# TheRightHandPath.net
KiCad netlist of a schematic drawn in EAGLE
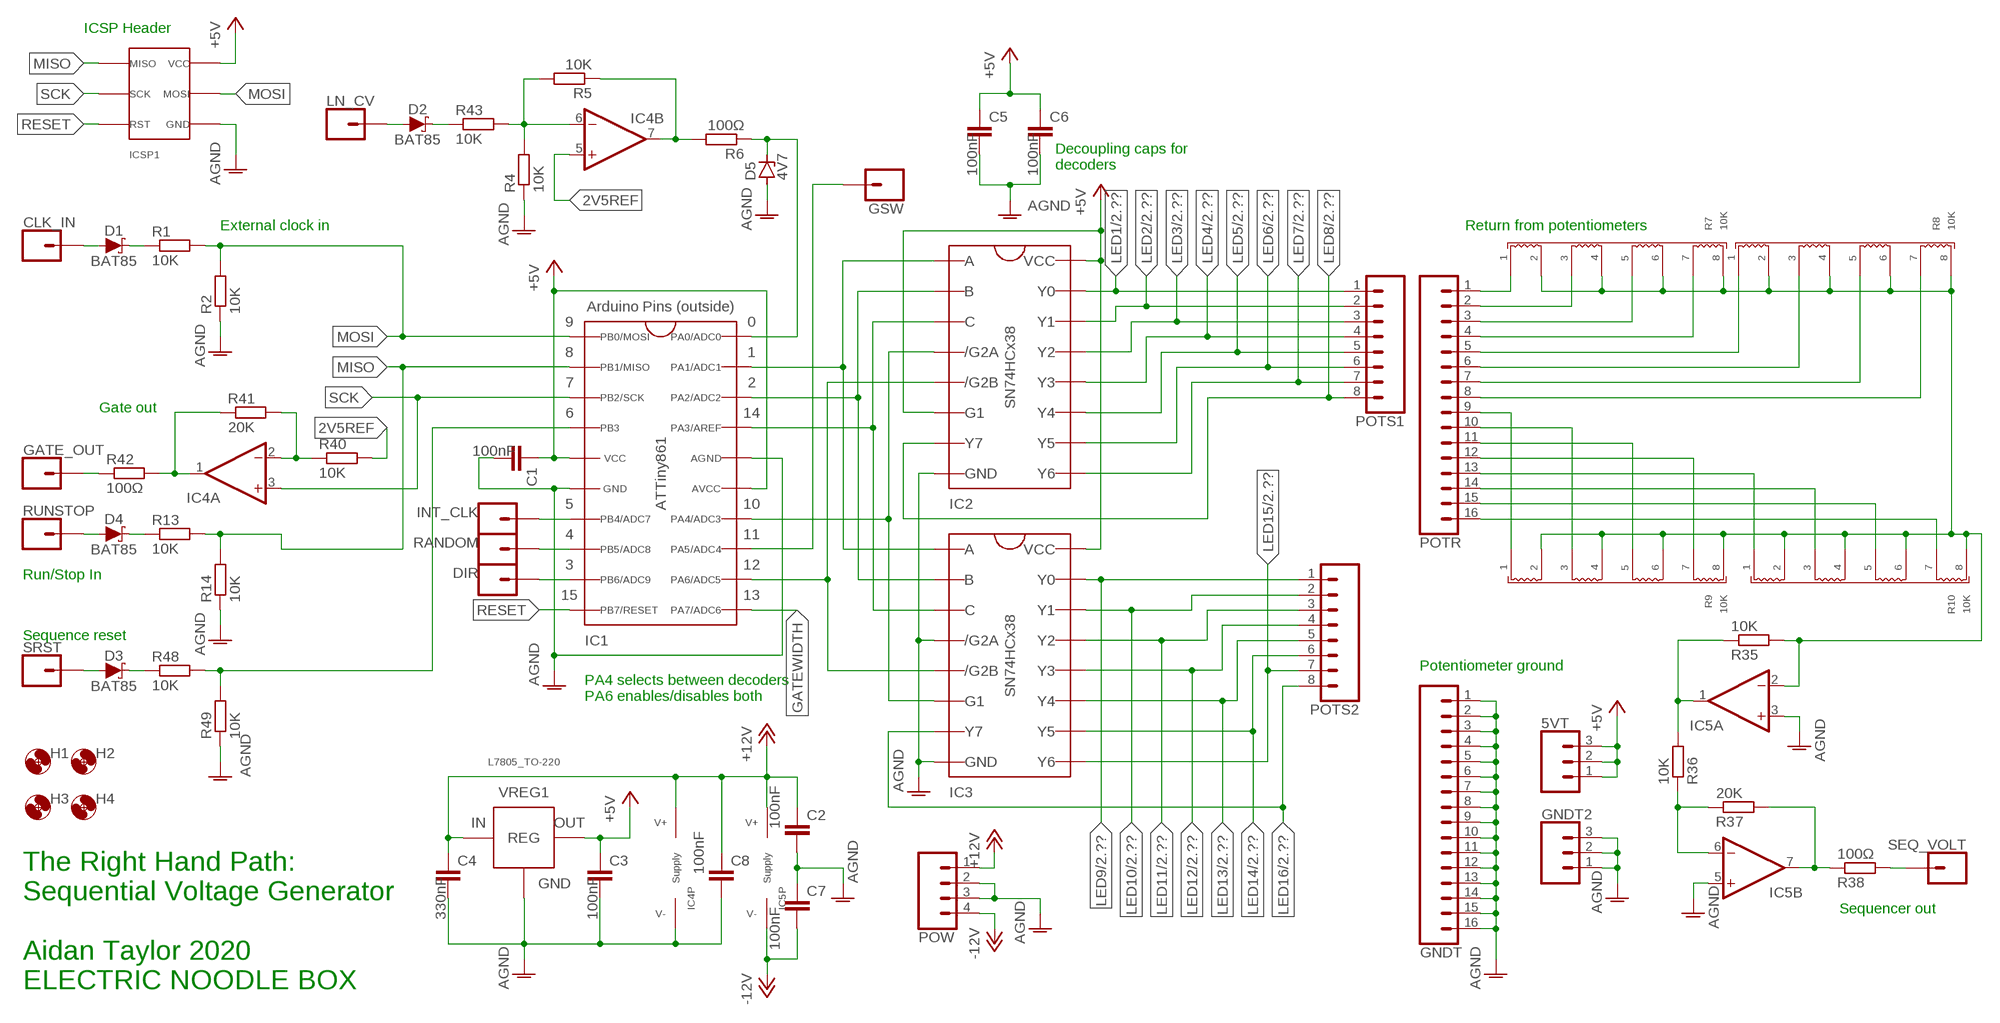
[diagram p0: schematic, sheet 1]
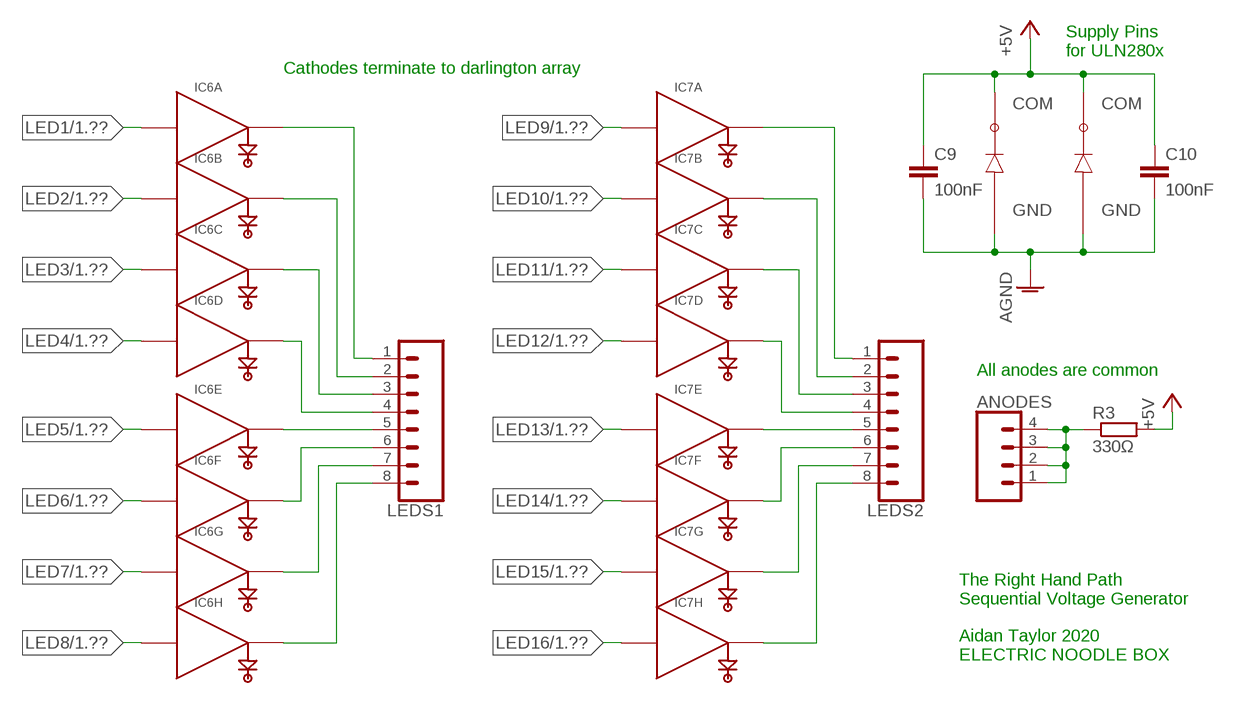
[diagram p1: schematic, sheet 2]

(export (version "E")
  (design (tool "Eeschema 10.0.6"))
  (components
    (comp (ref "ANODES")
      (value "4XWIREPAD")
      (footprint "eagle-import:1X04")
      (libsource (lib "eagle-import") (part "4XWIREPAD"))
    )
    (comp (ref "C9")
      (value "100nF")
      (footprint "eagle-import:C050-025X075")
      (libsource (lib "eagle-import") (part "C-EU050-025X075"))
    )
    (comp (ref "C10")
      (value "100nF")
      (footprint "eagle-import:C050-025X075")
      (libsource (lib "eagle-import") (part "C-EU050-025X075"))
    )
    (comp (ref "IC6")
      (value "ULN2801_DIP")
      (footprint "eagle-import:DIL18")
      (libsource (lib "eagle-import") (part "ULN2801_DIP"))
    )
    (comp (ref "IC7")
      (value "ULN2801_DIP")
      (footprint "eagle-import:DIL18")
      (libsource (lib "eagle-import") (part "ULN2801_DIP"))
    )
    (comp (ref "LEDS1")
      (value "8XWIREPAD")
      (footprint "eagle-import:1X08")
      (libsource (lib "eagle-import") (part "8XWIREPAD"))
    )
    (comp (ref "LEDS2")
      (value "8XWIREPAD")
      (footprint "eagle-import:1X08")
      (libsource (lib "eagle-import") (part "8XWIREPAD"))
    )
    (comp (ref "R3")
      (value "330Ω")
      (footprint "eagle-import:0207_10")
      (libsource (lib "eagle-import") (part "R-EU_0207/10"))
    )
    (comp (ref "5VT")
      (value "3XWIREPAD")
      (footprint "eagle-import:1X03")
      (libsource (lib "eagle-import") (part "3XWIREPAD"))
    )
    (comp (ref "C1")
      (value "100nF")
      (footprint "eagle-import:C050-025X075")
      (libsource (lib "eagle-import") (part "C-EU050-025X075"))
    )
    (comp (ref "C2")
      (value "100nF")
      (footprint "eagle-import:C050-025X075")
      (libsource (lib "eagle-import") (part "C-EU050-025X075"))
    )
    (comp (ref "C3")
      (value "100nF")
      (footprint "eagle-import:C050-025X075")
      (libsource (lib "eagle-import") (part "C-EU050-025X075"))
    )
    (comp (ref "C4")
      (value "330nF")
      (footprint "eagle-import:C050-025X075")
      (libsource (lib "eagle-import") (part "C-EU050-025X075"))
    )
    (comp (ref "C5")
      (value "100nF")
      (footprint "eagle-import:C050-025X075")
      (libsource (lib "eagle-import") (part "C-EU050-025X075"))
    )
    (comp (ref "C6")
      (value "100nF")
      (footprint "eagle-import:C050-025X075")
      (libsource (lib "eagle-import") (part "C-EU050-025X075"))
    )
    (comp (ref "C7")
      (value "100nF")
      (footprint "eagle-import:C050-025X075")
      (libsource (lib "eagle-import") (part "C-EU050-025X075"))
    )
    (comp (ref "C8")
      (value "100nF")
      (footprint "eagle-import:C050-025X075")
      (libsource (lib "eagle-import") (part "C-EU050-025X075"))
    )
    (comp (ref "CLK_IN")
      (value "1XWIREPAD")
      (footprint "eagle-import:1X01")
      (libsource (lib "eagle-import") (part "1XWIREPAD"))
    )
    (comp (ref "D1")
      (value "BAT85")
      (footprint "eagle-import:DO35-7")
      (libsource (lib "eagle-import") (part "SCHOTTKY_DO35"))
    )
    (comp (ref "D2")
      (value "BAT85")
      (footprint "eagle-import:DO35-7")
      (libsource (lib "eagle-import") (part "SCHOTTKY_DO35"))
    )
    (comp (ref "D3")
      (value "BAT85")
      (footprint "eagle-import:DO35-7")
      (libsource (lib "eagle-import") (part "SCHOTTKY_DO35"))
    )
    (comp (ref "D4")
      (value "BAT85")
      (footprint "eagle-import:DO35-7")
      (libsource (lib "eagle-import") (part "SCHOTTKY_DO35"))
    )
    (comp (ref "D5")
      (value "4V7")
      (footprint "eagle-import:DO35Z10")
      (libsource (lib "eagle-import") (part "ZENER-DIODEDO35Z10"))
    )
    (comp (ref "DIR")
      (value "1XWIREPAD")
      (footprint "eagle-import:1X01")
      (libsource (lib "eagle-import") (part "1XWIREPAD"))
    )
    (comp (ref "GATE_OUT")
      (value "1XWIREPAD")
      (footprint "eagle-import:1X01")
      (libsource (lib "eagle-import") (part "1XWIREPAD"))
    )
    (comp (ref "GNDT")
      (value "16XWIREPAD")
      (footprint "eagle-import:1X16")
      (libsource (lib "eagle-import") (part "16XWIREPAD"))
    )
    (comp (ref "GNDT2")
      (value "3XWIREPAD")
      (footprint "eagle-import:1X03")
      (libsource (lib "eagle-import") (part "3XWIREPAD"))
    )
    (comp (ref "GSW")
      (value "1XWIREPAD")
      (footprint "eagle-import:1X01")
      (libsource (lib "eagle-import") (part "1XWIREPAD"))
    )
    (comp (ref "H1")
      (value "MOUNT-HOLE3.2")
      (footprint "eagle-import:3,2")
      (libsource (lib "eagle-import") (part "MOUNT-HOLE3.2"))
    )
    (comp (ref "H2")
      (value "MOUNT-HOLE3.2")
      (footprint "eagle-import:3,2")
      (libsource (lib "eagle-import") (part "MOUNT-HOLE3.2"))
    )
    (comp (ref "H3")
      (value "MOUNT-HOLE3.2")
      (footprint "eagle-import:3,2")
      (libsource (lib "eagle-import") (part "MOUNT-HOLE3.2"))
    )
    (comp (ref "H4")
      (value "MOUNT-HOLE3.2")
      (footprint "eagle-import:3,2")
      (libsource (lib "eagle-import") (part "MOUNT-HOLE3.2"))
    )
    (comp (ref "IC1")
      (value "ATTINY861_DIP")
      (footprint "eagle-import:DIL20")
      (libsource (lib "eagle-import") (part "ATTINY861_DIP"))
    )
    (comp (ref "IC2")
      (value "SN74HCX38")
      (footprint "eagle-import:DIL16")
      (libsource (lib "eagle-import") (part "SN74HCX38"))
    )
    (comp (ref "IC3")
      (value "SN74HCX38")
      (footprint "eagle-import:DIL16")
      (libsource (lib "eagle-import") (part "SN74HCX38"))
    )
    (comp (ref "IC4")
      (value "LM358_DIP")
      (footprint "eagle-import:DIL08")
      (libsource (lib "eagle-import") (part "LM358_DIP"))
    )
    (comp (ref "IC5")
      (value "TL0X2_DIP")
      (footprint "eagle-import:DIL08")
      (libsource (lib "eagle-import") (part "TL0X2_DIP"))
    )
    (comp (ref "ICSP1")
      (value "ICSP_2.54")
      (footprint "eagle-import:2X3")
      (libsource (lib "eagle-import") (part "ICSP_2.54"))
    )
    (comp (ref "INT_CLK")
      (value "1XWIREPAD")
      (footprint "eagle-import:1X01")
      (libsource (lib "eagle-import") (part "1XWIREPAD"))
    )
    (comp (ref "LN_CV")
      (value "1XWIREPAD")
      (footprint "eagle-import:1X01")
      (libsource (lib "eagle-import") (part "1XWIREPAD"))
    )
    (comp (ref "POTR")
      (value "16XWIREPAD")
      (footprint "eagle-import:1X16")
      (libsource (lib "eagle-import") (part "16XWIREPAD"))
    )
    (comp (ref "POTS1")
      (value "8XWIREPAD")
      (footprint "eagle-import:1X08")
      (libsource (lib "eagle-import") (part "8XWIREPAD"))
    )
    (comp (ref "POTS2")
      (value "8XWIREPAD")
      (footprint "eagle-import:1X08")
      (libsource (lib "eagle-import") (part "8XWIREPAD"))
    )
    (comp (ref "POW")
      (value "4XMOLEX")
      (footprint "eagle-import:MOLEX-1X4")
      (libsource (lib "eagle-import") (part "4XMOLEX"))
    )
    (comp (ref "R1")
      (value "10K")
      (footprint "eagle-import:0207_10")
      (libsource (lib "eagle-import") (part "R-EU_0207/10"))
    )
    (comp (ref "R2")
      (value "10K")
      (footprint "eagle-import:0207_10")
      (libsource (lib "eagle-import") (part "R-EU_0207/10"))
    )
    (comp (ref "R4")
      (value "10K")
      (footprint "eagle-import:0207_10")
      (libsource (lib "eagle-import") (part "R-EU_0207/10"))
    )
    (comp (ref "R5")
      (value "10K")
      (footprint "eagle-import:0207_10")
      (libsource (lib "eagle-import") (part "R-EU_0207/10"))
    )
    (comp (ref "R6")
      (value "100Ω")
      (footprint "eagle-import:0207_10")
      (libsource (lib "eagle-import") (part "R-EU_0207/10"))
    )
    (comp (ref "R7")
      (value "10K")
      (footprint "eagle-import:4_ISO_RES_NET_2.54")
      (libsource (lib "eagle-import") (part "4XISO_RESISTOR_NETWORK_2.54"))
    )
    (comp (ref "R8")
      (value "10K")
      (footprint "eagle-import:4_ISO_RES_NET_2.54")
      (libsource (lib "eagle-import") (part "4XISO_RESISTOR_NETWORK_2.54"))
    )
    (comp (ref "R9")
      (value "10K")
      (footprint "eagle-import:4_ISO_RES_NET_2.54")
      (libsource (lib "eagle-import") (part "4XISO_RESISTOR_NETWORK_2.54"))
    )
    (comp (ref "R10")
      (value "10K")
      (footprint "eagle-import:4_ISO_RES_NET_2.54")
      (libsource (lib "eagle-import") (part "4XISO_RESISTOR_NETWORK_2.54"))
    )
    (comp (ref "R13")
      (value "10K")
      (footprint "eagle-import:0207_10")
      (libsource (lib "eagle-import") (part "R-EU_0207/10"))
    )
    (comp (ref "R14")
      (value "10K")
      (footprint "eagle-import:0207_10")
      (libsource (lib "eagle-import") (part "R-EU_0207/10"))
    )
    (comp (ref "R35")
      (value "10K")
      (footprint "eagle-import:0207_10")
      (libsource (lib "eagle-import") (part "R-EU_0207/10"))
    )
    (comp (ref "R36")
      (value "10K")
      (footprint "eagle-import:0207_10")
      (libsource (lib "eagle-import") (part "R-EU_0207/10"))
    )
    (comp (ref "R37")
      (value "20K")
      (footprint "eagle-import:0207_10")
      (libsource (lib "eagle-import") (part "R-EU_0207/10"))
    )
    (comp (ref "R38")
      (value "100Ω")
      (footprint "eagle-import:0207_10")
      (libsource (lib "eagle-import") (part "R-EU_0207/10"))
    )
    (comp (ref "R40")
      (value "10K")
      (footprint "eagle-import:0207_10")
      (libsource (lib "eagle-import") (part "R-EU_0207/10"))
    )
    (comp (ref "R41")
      (value "20K")
      (footprint "eagle-import:0207_10")
      (libsource (lib "eagle-import") (part "R-EU_0207/10"))
    )
    (comp (ref "R42")
      (value "100Ω")
      (footprint "eagle-import:0207_10")
      (libsource (lib "eagle-import") (part "R-EU_0207/10"))
    )
    (comp (ref "R43")
      (value "10K")
      (footprint "eagle-import:0207_10")
      (libsource (lib "eagle-import") (part "R-EU_0207/10"))
    )
    (comp (ref "R48")
      (value "10K")
      (footprint "eagle-import:0207_10")
      (libsource (lib "eagle-import") (part "R-EU_0207/10"))
    )
    (comp (ref "R49")
      (value "10K")
      (footprint "eagle-import:0207_10")
      (libsource (lib "eagle-import") (part "R-EU_0207/10"))
    )
    (comp (ref "RANDOM")
      (value "1XWIREPAD")
      (footprint "eagle-import:1X01")
      (libsource (lib "eagle-import") (part "1XWIREPAD"))
    )
    (comp (ref "RUNSTOP")
      (value "1XWIREPAD")
      (footprint "eagle-import:1X01")
      (libsource (lib "eagle-import") (part "1XWIREPAD"))
    )
    (comp (ref "SEQ_VOLT")
      (value "1XWIREPAD")
      (footprint "eagle-import:1X01")
      (libsource (lib "eagle-import") (part "1XWIREPAD"))
    )
    (comp (ref "SRST")
      (value "1XWIREPAD")
      (footprint "eagle-import:1X01")
      (libsource (lib "eagle-import") (part "1XWIREPAD"))
    )
    (comp (ref "VREG1")
      (value "L7805_TO-220")
      (footprint "eagle-import:TO220H")
      (libsource (lib "eagle-import") (part "L7805_TO-220"))
    )
  )
  (nets
    (net (code "1") (name "+5V") (class "Default")
      (node (ref "5VT") (pin "1") (pinfunction "1_1") (pintype "passive"))
      (node (ref "5VT") (pin "2") (pinfunction "2_2") (pintype "passive"))
      (node (ref "5VT") (pin "3") (pinfunction "3_3") (pintype "passive"))
      (node (ref "C1") (pin "1") (pinfunction "1_1") (pintype "passive"))
      (node (ref "C10") (pin "1") (pinfunction "1_1") (pintype "passive"))
      (node (ref "C3") (pin "1") (pinfunction "1_1") (pintype "passive"))
      (node (ref "C5") (pin "1") (pinfunction "1_1") (pintype "passive"))
      (node (ref "C6") (pin "1") (pinfunction "1_1") (pintype "passive"))
      (node (ref "C9") (pin "1") (pinfunction "1_1") (pintype "passive"))
      (node (ref "IC1") (pin "15") (pinfunction "AVCC_15") (pintype "bidirectional"))
      (node (ref "IC1") (pin "5") (pinfunction "VCC_5") (pintype "power_in"))
      (node (ref "IC2") (pin "16") (pinfunction "16_VCC_16") (pintype "power_in"))
      (node (ref "IC2") (pin "6") (pinfunction "6_G1_6") (pintype "input"))
      (node (ref "IC3") (pin "16") (pinfunction "16_VCC_16") (pintype "power_in"))
      (node (ref "IC6") (pin "10") (pinfunction "COM_10") (pintype "power_in"))
      (node (ref "IC7") (pin "10") (pinfunction "COM_10") (pintype "power_in"))
      (node (ref "ICSP1") (pin "2") (pinfunction "6VCC_2") (pintype "power_in"))
      (node (ref "R3") (pin "2") (pinfunction "2_2") (pintype "passive"))
      (node (ref "VREG1") (pin "3") (pinfunction "VOUT_3") (pintype "output"))
    )
    (net (code "2") (name "+12V") (class "Default")
      (node (ref "C2") (pin "1") (pinfunction "1_1") (pintype "passive"))
      (node (ref "C4") (pin "1") (pinfunction "1_1") (pintype "passive"))
      (node (ref "C8") (pin "1") (pinfunction "1_1") (pintype "passive"))
      (node (ref "IC4") (pin "8") (pinfunction "V+_8") (pintype "bidirectional"))
      (node (ref "IC5") (pin "8") (pinfunction "V+_8") (pintype "bidirectional"))
      (node (ref "POW") (pin "1") (pinfunction "1_1") (pintype "passive"))
      (node (ref "VREG1") (pin "1") (pinfunction "VIN_1") (pintype "input"))
    )
    (net (code "3") (name "-12V") (class "Default")
      (node (ref "C7") (pin "2") (pinfunction "2_2") (pintype "passive"))
      (node (ref "IC5") (pin "4") (pinfunction "V-_4") (pintype "bidirectional"))
      (node (ref "POW") (pin "4") (pinfunction "4_4") (pintype "passive"))
    )
    (net (code "4") (name "2V5REF") (class "Default")
      (node (ref "IC4") (pin "5") (pinfunction "+IN_5") (pintype "input"))
      (node (ref "R40") (pin "2") (pinfunction "2_2") (pintype "passive"))
    )
    (net (code "5") (name "AGND") (class "Default")
      (node (ref "C1") (pin "2") (pinfunction "2_2") (pintype "passive"))
      (node (ref "C10") (pin "2") (pinfunction "2_2") (pintype "passive"))
      (node (ref "C2") (pin "2") (pinfunction "2_2") (pintype "passive"))
      (node (ref "C3") (pin "2") (pinfunction "2_2") (pintype "passive"))
      (node (ref "C4") (pin "2") (pinfunction "2_2") (pintype "passive"))
      (node (ref "C5") (pin "2") (pinfunction "2_2") (pintype "passive"))
      (node (ref "C6") (pin "2") (pinfunction "2_2") (pintype "passive"))
      (node (ref "C7") (pin "1") (pinfunction "1_1") (pintype "passive"))
      (node (ref "C8") (pin "2") (pinfunction "2_2") (pintype "passive"))
      (node (ref "C9") (pin "2") (pinfunction "2_2") (pintype "passive"))
      (node (ref "D5") (pin "A") (pinfunction "A_A") (pintype "passive"))
      (node (ref "GNDT") (pin "1") (pinfunction "1_1") (pintype "passive"))
      (node (ref "GNDT") (pin "10") (pinfunction "10_10") (pintype "passive"))
      (node (ref "GNDT") (pin "11") (pinfunction "11_11") (pintype "passive"))
      (node (ref "GNDT") (pin "12") (pinfunction "12_12") (pintype "passive"))
      (node (ref "GNDT") (pin "13") (pinfunction "13_13") (pintype "passive"))
      (node (ref "GNDT") (pin "14") (pinfunction "14_14") (pintype "passive"))
      (node (ref "GNDT") (pin "15") (pinfunction "15_15") (pintype "passive"))
      (node (ref "GNDT") (pin "16") (pinfunction "16_16") (pintype "passive"))
      (node (ref "GNDT") (pin "2") (pinfunction "2_2") (pintype "passive"))
      (node (ref "GNDT") (pin "3") (pinfunction "3_3") (pintype "passive"))
      (node (ref "GNDT") (pin "4") (pinfunction "4_4") (pintype "passive"))
      (node (ref "GNDT") (pin "5") (pinfunction "5_5") (pintype "passive"))
      (node (ref "GNDT") (pin "6") (pinfunction "6_6") (pintype "passive"))
      (node (ref "GNDT") (pin "7") (pinfunction "7_7") (pintype "passive"))
      (node (ref "GNDT") (pin "8") (pinfunction "8_8") (pintype "passive"))
      (node (ref "GNDT") (pin "9") (pinfunction "9_9") (pintype "passive"))
      (node (ref "GNDT2") (pin "1") (pinfunction "1_1") (pintype "passive"))
      (node (ref "GNDT2") (pin "2") (pinfunction "2_2") (pintype "passive"))
      (node (ref "GNDT2") (pin "3") (pinfunction "3_3") (pintype "passive"))
      (node (ref "IC1") (pin "16") (pinfunction "AGND_16") (pintype "bidirectional"))
      (node (ref "IC1") (pin "6") (pinfunction "GND_6") (pintype "power_in"))
      (node (ref "IC2") (pin "8") (pinfunction "8_GND_8") (pintype "power_in"))
      (node (ref "IC3") (pin "4") (pinfunction "4_/G2A_4") (pintype "input"))
      (node (ref "IC3") (pin "8") (pinfunction "8_GND_8") (pintype "power_in"))
      (node (ref "IC4") (pin "4") (pinfunction "V-_4") (pintype "bidirectional"))
      (node (ref "IC5") (pin "3") (pinfunction "+IN_3") (pintype "input"))
      (node (ref "IC5") (pin "5") (pinfunction "+IN_5") (pintype "input"))
      (node (ref "IC6") (pin "9") (pinfunction "GND_9") (pintype "power_in"))
      (node (ref "IC7") (pin "9") (pinfunction "GND_9") (pintype "power_in"))
      (node (ref "ICSP1") (pin "6") (pinfunction "4GND_6") (pintype "power_in"))
      (node (ref "POW") (pin "2") (pinfunction "2_2") (pintype "passive"))
      (node (ref "POW") (pin "3") (pinfunction "3_3") (pintype "passive"))
      (node (ref "R14") (pin "1") (pinfunction "1_1") (pintype "passive"))
      (node (ref "R2") (pin "1") (pinfunction "1_1") (pintype "passive"))
      (node (ref "R4") (pin "1") (pinfunction "1_1") (pintype "passive"))
      (node (ref "R49") (pin "1") (pinfunction "1_1") (pintype "passive"))
      (node (ref "VREG1") (pin "2") (pinfunction "GND_2") (pintype "power_in"))
    )
    (net (code "6") (name "GATEWIDTH") (class "Default")
      (node (ref "IC1") (pin "11") (pinfunction "11_PA7_11") (pintype "bidirectional"))
    )
    (net (code "7") (name "LED1") (class "Default")
      (node (ref "IC2") (pin "15") (pinfunction "15_Y0_15") (pintype "output"))
      (node (ref "IC6") (pin "1") (pinfunction "IN_1") (pintype "input"))
      (node (ref "POTS1") (pin "1") (pinfunction "1_1") (pintype "passive"))
    )
    (net (code "8") (name "LED2") (class "Default")
      (node (ref "IC2") (pin "14") (pinfunction "14_Y1_14") (pintype "output"))
      (node (ref "IC6") (pin "2") (pinfunction "IN_2") (pintype "input"))
      (node (ref "POTS1") (pin "2") (pinfunction "2_2") (pintype "passive"))
    )
    (net (code "9") (name "LED3") (class "Default")
      (node (ref "IC2") (pin "13") (pinfunction "13_Y2_13") (pintype "output"))
      (node (ref "IC6") (pin "3") (pinfunction "IN_3") (pintype "input"))
      (node (ref "POTS1") (pin "3") (pinfunction "3_3") (pintype "passive"))
    )
    (net (code "10") (name "LED4") (class "Default")
      (node (ref "IC2") (pin "12") (pinfunction "12_Y3_12") (pintype "output"))
      (node (ref "IC6") (pin "4") (pinfunction "IN_4") (pintype "input"))
      (node (ref "POTS1") (pin "4") (pinfunction "4_4") (pintype "passive"))
    )
    (net (code "11") (name "LED5") (class "Default")
      (node (ref "IC2") (pin "11") (pinfunction "11_Y4_11") (pintype "output"))
      (node (ref "IC6") (pin "5") (pinfunction "IN_5") (pintype "input"))
      (node (ref "POTS1") (pin "5") (pinfunction "5_5") (pintype "passive"))
    )
    (net (code "12") (name "LED6") (class "Default")
      (node (ref "IC2") (pin "10") (pinfunction "10_Y5_10") (pintype "output"))
      (node (ref "IC6") (pin "6") (pinfunction "IN_6") (pintype "input"))
      (node (ref "POTS1") (pin "6") (pinfunction "6_6") (pintype "passive"))
    )
    (net (code "13") (name "LED7") (class "Default")
      (node (ref "IC2") (pin "9") (pinfunction "9_Y6_9") (pintype "output"))
      (node (ref "IC6") (pin "7") (pinfunction "IN_7") (pintype "input"))
      (node (ref "POTS1") (pin "7") (pinfunction "7_7") (pintype "passive"))
    )
    (net (code "14") (name "LED8") (class "Default")
      (node (ref "IC2") (pin "7") (pinfunction "7_Y7_7") (pintype "output"))
      (node (ref "IC6") (pin "8") (pinfunction "IN_8") (pintype "input"))
      (node (ref "POTS1") (pin "8") (pinfunction "8_8") (pintype "passive"))
    )
    (net (code "15") (name "LED9") (class "Default")
      (node (ref "IC3") (pin "15") (pinfunction "15_Y0_15") (pintype "output"))
      (node (ref "IC7") (pin "1") (pinfunction "IN_1") (pintype "input"))
      (node (ref "POTS2") (pin "1") (pinfunction "1_1") (pintype "passive"))
    )
    (net (code "16") (name "LED10") (class "Default")
      (node (ref "IC3") (pin "14") (pinfunction "14_Y1_14") (pintype "output"))
      (node (ref "IC7") (pin "2") (pinfunction "IN_2") (pintype "input"))
      (node (ref "POTS2") (pin "2") (pinfunction "2_2") (pintype "passive"))
    )
    (net (code "17") (name "LED11") (class "Default")
      (node (ref "IC3") (pin "13") (pinfunction "13_Y2_13") (pintype "output"))
      (node (ref "IC7") (pin "3") (pinfunction "IN_3") (pintype "input"))
      (node (ref "POTS2") (pin "3") (pinfunction "3_3") (pintype "passive"))
    )
    (net (code "18") (name "LED12") (class "Default")
      (node (ref "IC3") (pin "12") (pinfunction "12_Y3_12") (pintype "output"))
      (node (ref "IC7") (pin "4") (pinfunction "IN_4") (pintype "input"))
      (node (ref "POTS2") (pin "4") (pinfunction "4_4") (pintype "passive"))
    )
    (net (code "19") (name "LED13") (class "Default")
      (node (ref "IC3") (pin "11") (pinfunction "11_Y4_11") (pintype "output"))
      (node (ref "IC7") (pin "5") (pinfunction "IN_5") (pintype "input"))
      (node (ref "POTS2") (pin "5") (pinfunction "5_5") (pintype "passive"))
    )
    (net (code "20") (name "LED14") (class "Default")
      (node (ref "IC3") (pin "10") (pinfunction "10_Y5_10") (pintype "output"))
      (node (ref "IC7") (pin "6") (pinfunction "IN_6") (pintype "input"))
      (node (ref "POTS2") (pin "6") (pinfunction "6_6") (pintype "passive"))
    )
    (net (code "21") (name "LED15") (class "Default")
      (node (ref "IC3") (pin "9") (pinfunction "9_Y6_9") (pintype "output"))
      (node (ref "IC7") (pin "7") (pinfunction "IN_7") (pintype "input"))
      (node (ref "POTS2") (pin "7") (pinfunction "7_7") (pintype "passive"))
    )
    (net (code "22") (name "LED16") (class "Default")
      (node (ref "IC3") (pin "7") (pinfunction "7_Y7_7") (pintype "output"))
      (node (ref "IC7") (pin "8") (pinfunction "IN_8") (pintype "input"))
      (node (ref "POTS2") (pin "8") (pinfunction "8_8") (pintype "passive"))
    )
    (net (code "23") (name "MISO") (class "Default")
      (node (ref "IC1") (pin "2") (pinfunction "2_PB1_2") (pintype "bidirectional"))
      (node (ref "ICSP1") (pin "1") (pinfunction "1MISO_1") (pintype "bidirectional"))
      (node (ref "R13") (pin "2") (pinfunction "2_2") (pintype "passive"))
      (node (ref "R14") (pin "2") (pinfunction "2_2") (pintype "passive"))
    )
    (net (code "24") (name "MOSI") (class "Default")
      (node (ref "IC1") (pin "1") (pinfunction "1_PB0_1") (pintype "bidirectional"))
      (node (ref "ICSP1") (pin "4") (pinfunction "5MOSI_4") (pintype "bidirectional"))
      (node (ref "R1") (pin "2") (pinfunction "2_2") (pintype "passive"))
      (node (ref "R2") (pin "2") (pinfunction "2_2") (pintype "passive"))
    )
    (net (code "25") (name "Net-(ANODES-Pad1)") (class "Default")
      (node (ref "ANODES") (pin "1") (pinfunction "1_1") (pintype "passive"))
      (node (ref "ANODES") (pin "2") (pinfunction "2_2") (pintype "passive"))
      (node (ref "ANODES") (pin "3") (pinfunction "3_3") (pintype "passive"))
      (node (ref "ANODES") (pin "4") (pinfunction "4_4") (pintype "passive"))
      (node (ref "R3") (pin "1") (pinfunction "1_1") (pintype "passive"))
    )
    (net (code "26") (name "Net-(CLK_IN-Pad1)") (class "Default")
      (node (ref "CLK_IN") (pin "1") (pinfunction "1_1") (pintype "passive"))
      (node (ref "D1") (pin "A") (pinfunction "A_A") (pintype "passive"))
    )
    (net (code "27") (name "Net-(D1-PadC)") (class "Default")
      (node (ref "D1") (pin "C") (pinfunction "C_C") (pintype "passive"))
      (node (ref "R1") (pin "1") (pinfunction "1_1") (pintype "passive"))
    )
    (net (code "28") (name "Net-(D2-PadA)") (class "Default")
      (node (ref "D2") (pin "A") (pinfunction "A_A") (pintype "passive"))
      (node (ref "LN_CV") (pin "1") (pinfunction "1_1") (pintype "passive"))
    )
    (net (code "29") (name "Net-(D2-PadC)") (class "Default")
      (node (ref "D2") (pin "C") (pinfunction "C_C") (pintype "passive"))
      (node (ref "R43") (pin "1") (pinfunction "1_1") (pintype "passive"))
    )
    (net (code "30") (name "Net-(D3-PadA)") (class "Default")
      (node (ref "D3") (pin "A") (pinfunction "A_A") (pintype "passive"))
      (node (ref "SRST") (pin "1") (pinfunction "1_1") (pintype "passive"))
    )
    (net (code "31") (name "Net-(D3-PadC)") (class "Default")
      (node (ref "D3") (pin "C") (pinfunction "C_C") (pintype "passive"))
      (node (ref "R48") (pin "1") (pinfunction "1_1") (pintype "passive"))
    )
    (net (code "32") (name "Net-(D4-PadA)") (class "Default")
      (node (ref "D4") (pin "A") (pinfunction "A_A") (pintype "passive"))
      (node (ref "RUNSTOP") (pin "1") (pinfunction "1_1") (pintype "passive"))
    )
    (net (code "33") (name "Net-(D4-PadC)") (class "Default")
      (node (ref "D4") (pin "C") (pinfunction "C_C") (pintype "passive"))
      (node (ref "R13") (pin "1") (pinfunction "1_1") (pintype "passive"))
    )
    (net (code "34") (name "Net-(GATE_OUT-Pad1)") (class "Default")
      (node (ref "GATE_OUT") (pin "1") (pinfunction "1_1") (pintype "passive"))
      (node (ref "R42") (pin "1") (pinfunction "1_1") (pintype "passive"))
    )
    (net (code "35") (name "Net-(IC1-4_PB3)") (class "Default")
      (node (ref "IC1") (pin "4") (pinfunction "4_PB3_4") (pintype "bidirectional"))
      (node (ref "R48") (pin "2") (pinfunction "2_2") (pintype "passive"))
      (node (ref "R49") (pin "2") (pinfunction "2_2") (pintype "passive"))
    )
    (net (code "36") (name "Net-(IC1-7_PB4)") (class "Default")
      (node (ref "IC1") (pin "7") (pinfunction "7_PB4_7") (pintype "bidirectional"))
      (node (ref "INT_CLK") (pin "1") (pinfunction "1_1") (pintype "passive"))
    )
    (net (code "37") (name "Net-(IC1-8_PB5)") (class "Default")
      (node (ref "IC1") (pin "8") (pinfunction "8_PB5_8") (pintype "bidirectional"))
      (node (ref "RANDOM") (pin "1") (pinfunction "1_1") (pintype "passive"))
    )
    (net (code "38") (name "Net-(IC1-9_PB6)") (class "Default")
      (node (ref "DIR") (pin "1") (pinfunction "1_1") (pintype "passive"))
      (node (ref "IC1") (pin "9") (pinfunction "9_PB6_9") (pintype "bidirectional"))
    )
    (net (code "39") (name "Net-(IC1-12_PA6)") (class "Default")
      (node (ref "IC1") (pin "12") (pinfunction "12_PA6_12") (pintype "bidirectional"))
      (node (ref "IC2") (pin "5") (pinfunction "5_/G2B_5") (pintype "input"))
      (node (ref "IC3") (pin "5") (pinfunction "5_/G2B_5") (pintype "input"))
    )
    (net (code "40") (name "Net-(IC1-13_PA5)") (class "Default")
      (node (ref "GSW") (pin "1") (pinfunction "1_1") (pintype "passive"))
      (node (ref "IC1") (pin "13") (pinfunction "13_PA5_13") (pintype "bidirectional"))
    )
    (net (code "41") (name "Net-(IC1-14_PA4)") (class "Default")
      (node (ref "IC1") (pin "14") (pinfunction "14_PA4_14") (pintype "bidirectional"))
      (node (ref "IC2") (pin "4") (pinfunction "4_/G2A_4") (pintype "input"))
      (node (ref "IC3") (pin "6") (pinfunction "6_G1_6") (pintype "input"))
    )
    (net (code "42") (name "Net-(IC1-17_PA3)") (class "Default")
      (node (ref "IC1") (pin "17") (pinfunction "17_PA3_17") (pintype "bidirectional"))
      (node (ref "IC2") (pin "3") (pinfunction "3_C_3") (pintype "input"))
      (node (ref "IC3") (pin "3") (pinfunction "3_C_3") (pintype "input"))
    )
    (net (code "43") (name "Net-(IC1-18_PA2)") (class "Default")
      (node (ref "IC1") (pin "18") (pinfunction "18_PA2_18") (pintype "bidirectional"))
      (node (ref "IC2") (pin "2") (pinfunction "2_B_2") (pintype "input"))
      (node (ref "IC3") (pin "2") (pinfunction "2_B_2") (pintype "input"))
    )
    (net (code "44") (name "Net-(IC1-19_PA1)") (class "Default")
      (node (ref "IC1") (pin "19") (pinfunction "19_PA1_19") (pintype "bidirectional"))
      (node (ref "IC2") (pin "1") (pinfunction "1_A_1") (pintype "input"))
      (node (ref "IC3") (pin "1") (pinfunction "1_A_1") (pintype "input"))
    )
    (net (code "45") (name "Net-(IC1-20_PA0)") (class "Default")
      (node (ref "D5") (pin "C") (pinfunction "C_C") (pintype "passive"))
      (node (ref "IC1") (pin "20") (pinfunction "20_PA0_20") (pintype "bidirectional"))
      (node (ref "R6") (pin "1") (pinfunction "1_1") (pintype "passive"))
    )
    (net (code "46") (name "Net-(IC4A--IN)") (class "Default")
      (node (ref "IC4") (pin "2") (pinfunction "-IN_2") (pintype "input"))
      (node (ref "R40") (pin "1") (pinfunction "1_1") (pintype "passive"))
      (node (ref "R41") (pin "2") (pinfunction "2_2") (pintype "passive"))
    )
    (net (code "47") (name "Net-(IC4A-OUT)") (class "Default")
      (node (ref "IC4") (pin "1") (pinfunction "OUT_1") (pintype "output"))
      (node (ref "R41") (pin "1") (pinfunction "1_1") (pintype "passive"))
      (node (ref "R42") (pin "2") (pinfunction "2_2") (pintype "passive"))
    )
    (net (code "48") (name "Net-(IC4B--IN)") (class "Default")
      (node (ref "IC4") (pin "6") (pinfunction "-IN_6") (pintype "input"))
      (node (ref "R4") (pin "2") (pinfunction "2_2") (pintype "passive"))
      (node (ref "R43") (pin "2") (pinfunction "2_2") (pintype "passive"))
      (node (ref "R5") (pin "2") (pinfunction "2_2") (pintype "passive"))
    )
    (net (code "49") (name "Net-(IC4B-OUT)") (class "Default")
      (node (ref "IC4") (pin "7") (pinfunction "OUT_7") (pintype "output"))
      (node (ref "R5") (pin "1") (pinfunction "1_1") (pintype "passive"))
      (node (ref "R6") (pin "2") (pinfunction "2_2") (pintype "passive"))
    )
    (net (code "50") (name "Net-(IC5A--IN)") (class "Default")
      (node (ref "IC5") (pin "2") (pinfunction "-IN_2") (pintype "input"))
      (node (ref "R10") (pin "P$2") (pinfunction "P$2_P$2") (pintype "bidirectional"))
      (node (ref "R10") (pin "P$4") (pinfunction "P$4_P$4") (pintype "bidirectional"))
      (node (ref "R10") (pin "P$6") (pinfunction "P$6_P$6") (pintype "bidirectional"))
      (node (ref "R10") (pin "P$8") (pinfunction "P$8_P$8") (pintype "bidirectional"))
      (node (ref "R35") (pin "2") (pinfunction "2_2") (pintype "passive"))
      (node (ref "R7") (pin "P$2") (pinfunction "P$2_P$2") (pintype "bidirectional"))
      (node (ref "R7") (pin "P$4") (pinfunction "P$4_P$4") (pintype "bidirectional"))
      (node (ref "R7") (pin "P$6") (pinfunction "P$6_P$6") (pintype "bidirectional"))
      (node (ref "R7") (pin "P$8") (pinfunction "P$8_P$8") (pintype "bidirectional"))
      (node (ref "R8") (pin "P$2") (pinfunction "P$2_P$2") (pintype "bidirectional"))
      (node (ref "R8") (pin "P$4") (pinfunction "P$4_P$4") (pintype "bidirectional"))
      (node (ref "R8") (pin "P$6") (pinfunction "P$6_P$6") (pintype "bidirectional"))
      (node (ref "R8") (pin "P$8") (pinfunction "P$8_P$8") (pintype "bidirectional"))
      (node (ref "R9") (pin "P$2") (pinfunction "P$2_P$2") (pintype "bidirectional"))
      (node (ref "R9") (pin "P$4") (pinfunction "P$4_P$4") (pintype "bidirectional"))
      (node (ref "R9") (pin "P$6") (pinfunction "P$6_P$6") (pintype "bidirectional"))
      (node (ref "R9") (pin "P$8") (pinfunction "P$8_P$8") (pintype "bidirectional"))
    )
    (net (code "51") (name "Net-(IC5A-OUT)") (class "Default")
      (node (ref "IC5") (pin "1") (pinfunction "OUT_1") (pintype "output"))
      (node (ref "R35") (pin "1") (pinfunction "1_1") (pintype "passive"))
      (node (ref "R36") (pin "2") (pinfunction "2_2") (pintype "passive"))
    )
    (net (code "52") (name "Net-(IC5B--IN)") (class "Default")
      (node (ref "IC5") (pin "6") (pinfunction "-IN_6") (pintype "input"))
      (node (ref "R36") (pin "1") (pinfunction "1_1") (pintype "passive"))
      (node (ref "R37") (pin "1") (pinfunction "1_1") (pintype "passive"))
    )
    (net (code "53") (name "Net-(IC5B-OUT)") (class "Default")
      (node (ref "IC5") (pin "7") (pinfunction "OUT_7") (pintype "output"))
      (node (ref "R37") (pin "2") (pinfunction "2_2") (pintype "passive"))
      (node (ref "R38") (pin "1") (pinfunction "1_1") (pintype "passive"))
    )
    (net (code "54") (name "Net-(IC6A-P$2)") (class "Default")
      (node (ref "IC6") (pin "18") (pinfunction "P$2_18") (pintype "output"))
      (node (ref "LEDS1") (pin "1") (pinfunction "1_1") (pintype "passive"))
    )
    (net (code "55") (name "Net-(IC6B-P$2)") (class "Default")
      (node (ref "IC6") (pin "17") (pinfunction "P$2_17") (pintype "output"))
      (node (ref "LEDS1") (pin "2") (pinfunction "2_2") (pintype "passive"))
    )
    (net (code "56") (name "Net-(IC6C-P$2)") (class "Default")
      (node (ref "IC6") (pin "16") (pinfunction "P$2_16") (pintype "output"))
      (node (ref "LEDS1") (pin "3") (pinfunction "3_3") (pintype "passive"))
    )
    (net (code "57") (name "Net-(IC6D-P$2)") (class "Default")
      (node (ref "IC6") (pin "15") (pinfunction "P$2_15") (pintype "output"))
      (node (ref "LEDS1") (pin "4") (pinfunction "4_4") (pintype "passive"))
    )
    (net (code "58") (name "Net-(IC6E-P$2)") (class "Default")
      (node (ref "IC6") (pin "14") (pinfunction "P$2_14") (pintype "output"))
      (node (ref "LEDS1") (pin "5") (pinfunction "5_5") (pintype "passive"))
    )
    (net (code "59") (name "Net-(IC6F-P$2)") (class "Default")
      (node (ref "IC6") (pin "13") (pinfunction "P$2_13") (pintype "output"))
      (node (ref "LEDS1") (pin "6") (pinfunction "6_6") (pintype "passive"))
    )
    (net (code "60") (name "Net-(IC6G-P$2)") (class "Default")
      (node (ref "IC6") (pin "12") (pinfunction "P$2_12") (pintype "output"))
      (node (ref "LEDS1") (pin "7") (pinfunction "7_7") (pintype "passive"))
    )
    (net (code "61") (name "Net-(IC6I-P$2)") (class "Default")
      (node (ref "IC6") (pin "11") (pinfunction "P$2_11") (pintype "output"))
      (node (ref "LEDS1") (pin "8") (pinfunction "8_8") (pintype "passive"))
    )
    (net (code "62") (name "Net-(IC7A-P$2)") (class "Default")
      (node (ref "IC7") (pin "18") (pinfunction "P$2_18") (pintype "output"))
      (node (ref "LEDS2") (pin "1") (pinfunction "1_1") (pintype "passive"))
    )
    (net (code "63") (name "Net-(IC7B-P$2)") (class "Default")
      (node (ref "IC7") (pin "17") (pinfunction "P$2_17") (pintype "output"))
      (node (ref "LEDS2") (pin "2") (pinfunction "2_2") (pintype "passive"))
    )
    (net (code "64") (name "Net-(IC7C-P$2)") (class "Default")
      (node (ref "IC7") (pin "16") (pinfunction "P$2_16") (pintype "output"))
      (node (ref "LEDS2") (pin "3") (pinfunction "3_3") (pintype "passive"))
    )
    (net (code "65") (name "Net-(IC7D-P$2)") (class "Default")
      (node (ref "IC7") (pin "15") (pinfunction "P$2_15") (pintype "output"))
      (node (ref "LEDS2") (pin "4") (pinfunction "4_4") (pintype "passive"))
    )
    (net (code "66") (name "Net-(IC7E-P$2)") (class "Default")
      (node (ref "IC7") (pin "14") (pinfunction "P$2_14") (pintype "output"))
      (node (ref "LEDS2") (pin "5") (pinfunction "5_5") (pintype "passive"))
    )
    (net (code "67") (name "Net-(IC7F-P$2)") (class "Default")
      (node (ref "IC7") (pin "13") (pinfunction "P$2_13") (pintype "output"))
      (node (ref "LEDS2") (pin "6") (pinfunction "6_6") (pintype "passive"))
    )
    (net (code "68") (name "Net-(IC7G-P$2)") (class "Default")
      (node (ref "IC7") (pin "12") (pinfunction "P$2_12") (pintype "output"))
      (node (ref "LEDS2") (pin "7") (pinfunction "7_7") (pintype "passive"))
    )
    (net (code "69") (name "Net-(IC7I-P$2)") (class "Default")
      (node (ref "IC7") (pin "11") (pinfunction "P$2_11") (pintype "output"))
      (node (ref "LEDS2") (pin "8") (pinfunction "8_8") (pintype "passive"))
    )
    (net (code "70") (name "Net-(POTR-Pad1)") (class "Default")
      (node (ref "POTR") (pin "1") (pinfunction "1_1") (pintype "passive"))
      (node (ref "R7") (pin "P$1") (pinfunction "P$1_P$1") (pintype "bidirectional"))
    )
    (net (code "71") (name "Net-(POTR-Pad2)") (class "Default")
      (node (ref "POTR") (pin "2") (pinfunction "2_2") (pintype "passive"))
      (node (ref "R7") (pin "P$3") (pinfunction "P$3_P$3") (pintype "bidirectional"))
    )
    (net (code "72") (name "Net-(POTR-Pad3)") (class "Default")
      (node (ref "POTR") (pin "3") (pinfunction "3_3") (pintype "passive"))
      (node (ref "R7") (pin "P$5") (pinfunction "P$5_P$5") (pintype "bidirectional"))
    )
    (net (code "73") (name "Net-(POTR-Pad4)") (class "Default")
      (node (ref "POTR") (pin "4") (pinfunction "4_4") (pintype "passive"))
      (node (ref "R7") (pin "P$7") (pinfunction "P$7_P$7") (pintype "bidirectional"))
    )
    (net (code "74") (name "Net-(POTR-Pad5)") (class "Default")
      (node (ref "POTR") (pin "5") (pinfunction "5_5") (pintype "passive"))
      (node (ref "R8") (pin "P$1") (pinfunction "P$1_P$1") (pintype "bidirectional"))
    )
    (net (code "75") (name "Net-(POTR-Pad6)") (class "Default")
      (node (ref "POTR") (pin "6") (pinfunction "6_6") (pintype "passive"))
      (node (ref "R8") (pin "P$3") (pinfunction "P$3_P$3") (pintype "bidirectional"))
    )
    (net (code "76") (name "Net-(POTR-Pad7)") (class "Default")
      (node (ref "POTR") (pin "7") (pinfunction "7_7") (pintype "passive"))
      (node (ref "R8") (pin "P$5") (pinfunction "P$5_P$5") (pintype "bidirectional"))
    )
    (net (code "77") (name "Net-(POTR-Pad8)") (class "Default")
      (node (ref "POTR") (pin "8") (pinfunction "8_8") (pintype "passive"))
      (node (ref "R8") (pin "P$7") (pinfunction "P$7_P$7") (pintype "bidirectional"))
    )
    (net (code "78") (name "Net-(POTR-Pad9)") (class "Default")
      (node (ref "POTR") (pin "9") (pinfunction "9_9") (pintype "passive"))
      (node (ref "R9") (pin "P$1") (pinfunction "P$1_P$1") (pintype "bidirectional"))
    )
    (net (code "79") (name "Net-(POTR-Pad10)") (class "Default")
      (node (ref "POTR") (pin "10") (pinfunction "10_10") (pintype "passive"))
      (node (ref "R9") (pin "P$3") (pinfunction "P$3_P$3") (pintype "bidirectional"))
    )
    (net (code "80") (name "Net-(POTR-Pad11)") (class "Default")
      (node (ref "POTR") (pin "11") (pinfunction "11_11") (pintype "passive"))
      (node (ref "R9") (pin "P$5") (pinfunction "P$5_P$5") (pintype "bidirectional"))
    )
    (net (code "81") (name "Net-(POTR-Pad12)") (class "Default")
      (node (ref "POTR") (pin "12") (pinfunction "12_12") (pintype "passive"))
      (node (ref "R9") (pin "P$7") (pinfunction "P$7_P$7") (pintype "bidirectional"))
    )
    (net (code "82") (name "Net-(POTR-Pad13)") (class "Default")
      (node (ref "POTR") (pin "13") (pinfunction "13_13") (pintype "passive"))
      (node (ref "R10") (pin "P$1") (pinfunction "P$1_P$1") (pintype "bidirectional"))
    )
    (net (code "83") (name "Net-(POTR-Pad14)") (class "Default")
      (node (ref "POTR") (pin "14") (pinfunction "14_14") (pintype "passive"))
      (node (ref "R10") (pin "P$3") (pinfunction "P$3_P$3") (pintype "bidirectional"))
    )
    (net (code "84") (name "Net-(POTR-Pad15)") (class "Default")
      (node (ref "POTR") (pin "15") (pinfunction "15_15") (pintype "passive"))
      (node (ref "R10") (pin "P$5") (pinfunction "P$5_P$5") (pintype "bidirectional"))
    )
    (net (code "85") (name "Net-(POTR-Pad16)") (class "Default")
      (node (ref "POTR") (pin "16") (pinfunction "16_16") (pintype "passive"))
      (node (ref "R10") (pin "P$7") (pinfunction "P$7_P$7") (pintype "bidirectional"))
    )
    (net (code "86") (name "Net-(R38-Pad2)") (class "Default")
      (node (ref "R38") (pin "2") (pinfunction "2_2") (pintype "passive"))
      (node (ref "SEQ_VOLT") (pin "1") (pinfunction "1_1") (pintype "passive"))
    )
    (net (code "87") (name "RESET") (class "Default")
      (node (ref "IC1") (pin "10") (pinfunction "10_PB7_10") (pintype "bidirectional"))
      (node (ref "ICSP1") (pin "5") (pinfunction "3RST_5") (pintype "bidirectional"))
    )
    (net (code "88") (name "SCK") (class "Default")
      (node (ref "IC1") (pin "3") (pinfunction "3_PB2_3") (pintype "bidirectional"))
      (node (ref "IC4") (pin "3") (pinfunction "+IN_3") (pintype "input"))
      (node (ref "ICSP1") (pin "3") (pinfunction "2SCK_3") (pintype "bidirectional"))
    )
  )
)
